# Input_channel.net
KiCad netlist of a schematic drawn in Altium Designer
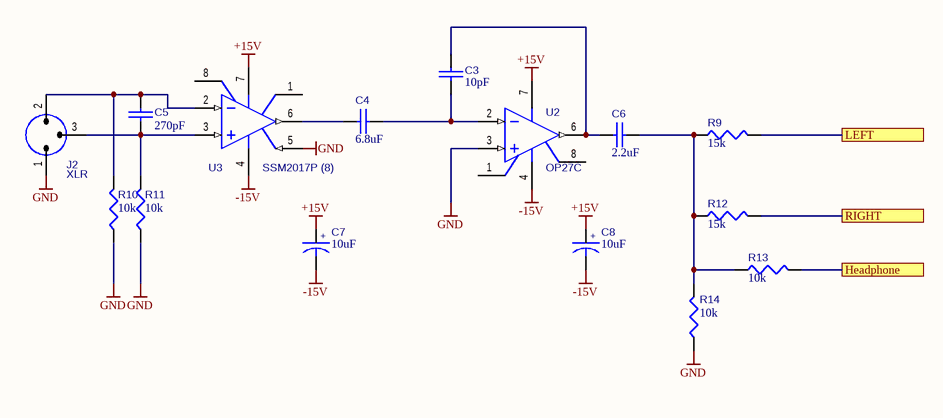
[diagram p0: Input channel.SchDoc]

(export (version "E")
  (design (tool "Eeschema 10.0.6"))
  (components
    (comp (ref "C3")
      (value "10pF")
      (footprint "RAD0.2")
      (description "Capacitor")
      (libsource (lib "*") (part "CAP"))
    )
    (comp (ref "C4")
      (value "6.8uF")
      (footprint "RB.2/.4-NP")
      (description "Capacitor")
      (libsource (lib "*") (part "CAP"))
    )
    (comp (ref "C5")
      (value "270pF")
      (footprint "RAD0.2")
      (description "Capacitor")
      (libsource (lib "*") (part "CAP"))
    )
    (comp (ref "C6")
      (value "2.2uF")
      (footprint "RB.2/.4-NP")
      (description "Capacitor")
      (libsource (lib "*") (part "CAP"))
    )
    (comp (ref "C7")
      (value "10uF")
      (footprint "RB.2/.4")
      (description "Bi-Polar Capacitor")
      (libsource (lib "*") (part "CAPACITOR POL"))
    )
    (comp (ref "C8")
      (value "10uF")
      (footprint "RB.2/.4")
      (description "Bi-Polar Capacitor")
      (libsource (lib "*") (part "CAPACITOR POL"))
    )
    (comp (ref "J2")
      (value "XLR")
      (footprint "XLR-FEMALE")
      (description "XLR connector, PCB mounted")
      (libsource (lib "*") (part "XLR"))
    )
    (comp (ref "R9")
      (value "15k")
      (footprint "AXIAL0.4")
      (description "Resistor")
      (libsource (lib "*") (part "RES1"))
    )
    (comp (ref "R10")
      (value "10k")
      (footprint "AXIAL0.4")
      (description "Resistor")
      (libsource (lib "") (part "RES1_1"))
    )
    (comp (ref "R11")
      (value "10k")
      (footprint "AXIAL0.4")
      (description "Resistor")
      (libsource (lib "") (part "RES1_1"))
    )
    (comp (ref "R12")
      (value "15k")
      (footprint "AXIAL0.4")
      (description "Resistor")
      (libsource (lib "*") (part "RES1"))
    )
    (comp (ref "R13")
      (value "10k")
      (footprint "AXIAL0.4")
      (description "Resistor")
      (libsource (lib "*") (part "RES1"))
    )
    (comp (ref "R14")
      (value "10k")
      (footprint "AXIAL0.4")
      (description "Resistor")
      (libsource (lib "") (part "RES1_1"))
    )
    (comp (ref "U2")
      (value "OP27C")
      (footprint "DIP8")
      (description "Low Noise, High Speed Precision Operational Amplifier")
      (libsource (lib "*") (part "OP27C"))
    )
    (comp (ref "U3")
      (value "SSM2017P (8)")
      (footprint "DIP8")
      (description "Self-Contained Audio Preamplifier")
      (libsource (lib "*") (part "SSM2017P (8)"))
    )
  )
  (nets
    (net (code "1") (name "+15V") (class "Default")
      (node (ref "C7") (pin "1") (pinfunction "1_1") (pintype "passive"))
      (node (ref "C8") (pin "1") (pinfunction "1_1") (pintype "passive"))
      (node (ref "U2") (pin "7") (pinfunction "V+_7") (pintype "power_in"))
      (node (ref "U3") (pin "7") (pinfunction "V+_7") (pintype "power_in"))
    )
    (net (code "2") (name "-15V") (class "Default")
      (node (ref "C7") (pin "2") (pinfunction "2_2") (pintype "passive"))
      (node (ref "C8") (pin "2") (pinfunction "2_2") (pintype "passive"))
      (node (ref "U2") (pin "4") (pinfunction "V-_4") (pintype "power_in"))
      (node (ref "U3") (pin "4") (pinfunction "V-_4") (pintype "power_in"))
    )
    (net (code "3") (name "/Headphone") (class "Default")
      (node (ref "R13") (pin "2") (pinfunction "2_2") (pintype "passive"))
    )
    (net (code "4") (name "/LEFT") (class "Default")
      (node (ref "R9") (pin "2") (pinfunction "2_2") (pintype "passive"))
    )
    (net (code "5") (name "/RIGHT") (class "Default")
      (node (ref "R12") (pin "2") (pinfunction "2_2") (pintype "passive"))
    )
    (net (code "6") (name "GND") (class "Default")
      (node (ref "J2") (pin "1") (pinfunction "1_1") (pintype "passive"))
      (node (ref "R10") (pin "1") (pinfunction "1_1") (pintype "passive"))
      (node (ref "R11") (pin "1") (pinfunction "1_1") (pintype "passive"))
      (node (ref "R14") (pin "1") (pinfunction "1_1") (pintype "passive"))
      (node (ref "U2") (pin "3") (pinfunction "+IN_3") (pintype "input"))
      (node (ref "U3") (pin "5") (pinfunction "REF_5") (pintype "input"))
    )
    (net (code "7") (name "Net-(C6-Pad2)") (class "Default")
      (node (ref "C6") (pin "2") (pinfunction "2_2") (pintype "passive"))
      (node (ref "R12") (pin "1") (pinfunction "1_1") (pintype "passive"))
      (node (ref "R13") (pin "1") (pinfunction "1_1") (pintype "passive"))
      (node (ref "R14") (pin "2") (pinfunction "2_2") (pintype "passive"))
      (node (ref "R9") (pin "1") (pinfunction "1_1") (pintype "passive"))
    )
    (net (code "8") (name "Net-(U2--IN)") (class "Default")
      (node (ref "C3") (pin "1") (pinfunction "1_1") (pintype "passive"))
      (node (ref "C4") (pin "2") (pinfunction "2_2") (pintype "passive"))
      (node (ref "U2") (pin "2") (pinfunction "-IN_2") (pintype "input"))
    )
    (net (code "9") (name "Net-(U2-OUT)") (class "Default")
      (node (ref "C3") (pin "2") (pinfunction "2_2") (pintype "passive"))
      (node (ref "C6") (pin "1") (pinfunction "1_1") (pintype "passive"))
      (node (ref "U2") (pin "6") (pinfunction "OUT_6") (pintype "output"))
    )
    (net (code "10") (name "Net-(U3-IN+)") (class "Default")
      (node (ref "C5") (pin "2") (pinfunction "2_2") (pintype "passive"))
      (node (ref "J2") (pin "3") (pinfunction "3_3") (pintype "passive"))
      (node (ref "R11") (pin "2") (pinfunction "2_2") (pintype "passive"))
      (node (ref "U3") (pin "3") (pinfunction "IN+_3") (pintype "input"))
    )
    (net (code "11") (name "Net-(U3-IN-)") (class "Default")
      (node (ref "C5") (pin "1") (pinfunction "1_1") (pintype "passive"))
      (node (ref "J2") (pin "2") (pinfunction "2_2") (pintype "passive"))
      (node (ref "R10") (pin "2") (pinfunction "2_2") (pintype "passive"))
      (node (ref "U3") (pin "2") (pinfunction "IN-_2") (pintype "input"))
    )
    (net (code "12") (name "Net-(U3-OUT)") (class "Default")
      (node (ref "C4") (pin "1") (pinfunction "1_1") (pintype "passive"))
      (node (ref "U3") (pin "6") (pinfunction "OUT_6") (pintype "output"))
    )
    (net (code "13") (name "unconnected-(U2-TRIM-Pad1)") (class "Default")
      (node (ref "U2") (pin "1") (pinfunction "TRIM_1") (pintype "passive"))
    )
    (net (code "14") (name "unconnected-(U2-TRIM-Pad8)") (class "Default")
      (node (ref "U2") (pin "8") (pinfunction "TRIM_8") (pintype "passive"))
    )
    (net (code "15") (name "unconnected-(U3-RG1-Pad1)") (class "Default")
      (node (ref "U3") (pin "1") (pinfunction "RG1_1") (pintype "passive"))
    )
    (net (code "16") (name "unconnected-(U3-RG2-Pad8)") (class "Default")
      (node (ref "U3") (pin "8") (pinfunction "RG2_8") (pintype "passive"))
    )
  )
)
